# BpodTeensyShield.net
KiCad netlist of a schematic drawn in EAGLE
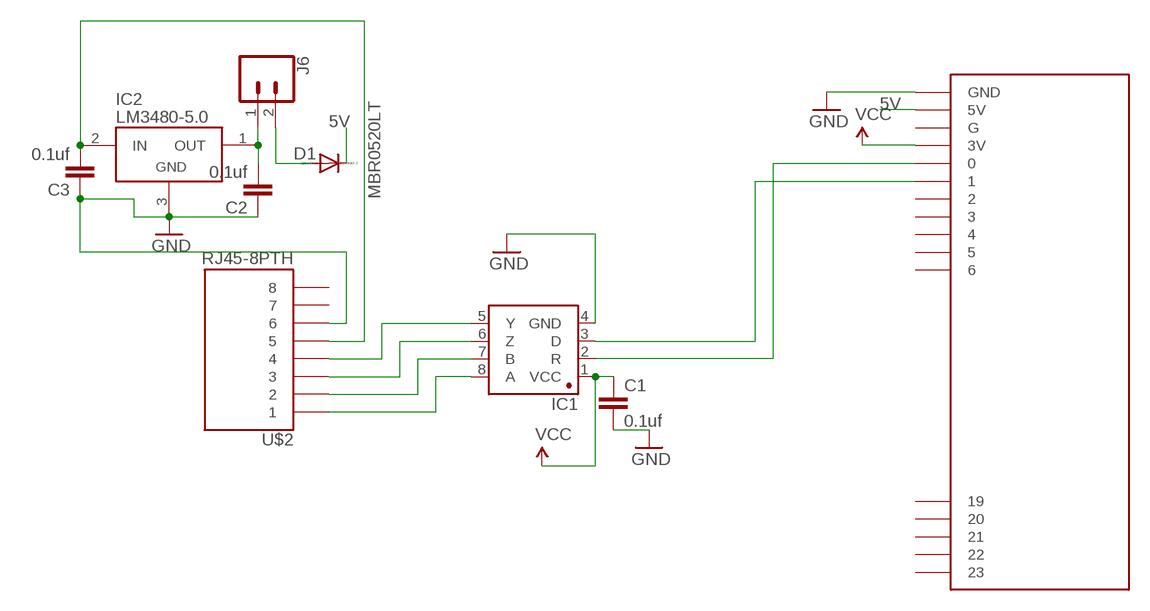
[diagram p0: schematic, sheet 1]

(export (version "E")
  (design (tool "Eeschema 10.0.6"))
  (components
    (comp (ref "C1")
      (value "0.1uf")
      (footprint "eagle-import:1206@1")
      (libsource (lib "eagle-import") (part "CAP1206"))
    )
    (comp (ref "C2")
      (value "0.1uf")
      (footprint "eagle-import:1206@1")
      (libsource (lib "eagle-import") (part "CAP1206"))
    )
    (comp (ref "C3")
      (value "0.1uf")
      (footprint "eagle-import:1206@1")
      (libsource (lib "eagle-import") (part "CAP1206"))
    )
    (comp (ref "D1")
      (value "MBR0520LT")
      (footprint "eagle-import:SOD123")
      (libsource (lib "eagle-import") (part "MBR0520LT"))
    )
    (comp (ref "IC1")
      (value "SN65HVD31DR")
      (footprint "eagle-import:SO08")
      (libsource (lib "eagle-import") (part "SN65HVD31DR"))
    )
    (comp (ref "IC2")
      (value "LM3480-5.0")
      (footprint "eagle-import:SOT-23-3")
      (libsource (lib "eagle-import") (part "LM3480-5.0"))
    )
    (comp (ref "J6")
      (value "CONN_02")
      (footprint "eagle-import:1X02")
      (libsource (lib "eagle-import") (part "CONN_02"))
    )
    (comp (ref "U$1")
      (value "AUDIOSHIELD")
      (footprint "eagle-import:AUDIOSHIELD")
      (libsource (lib "eagle-import") (part "AUDIOSHIELD"))
    )
    (comp (ref "U$2")
      (value "RJ45-8PTH")
      (footprint "eagle-import:RJ45-8")
      (libsource (lib "eagle-import") (part "RJ45-8PTH"))
    )
  )
  (nets
    (net (code "1") (name "/5V") (class "Default")
      (node (ref "D1") (pin "C") (pinfunction "C_C") (pintype "passive"))
      (node (ref "U$1") (pin "5V") (pinfunction "5V_5V") (pintype "bidirectional"))
    )
    (net (code "2") (name "GND") (class "Default")
      (node (ref "C1") (pin "2") (pinfunction "2_2") (pintype "passive"))
      (node (ref "C2") (pin "1") (pinfunction "1_1") (pintype "passive"))
      (node (ref "C3") (pin "1") (pinfunction "1_1") (pintype "passive"))
      (node (ref "IC1") (pin "4") (pinfunction "GND_4") (pintype "bidirectional"))
      (node (ref "IC2") (pin "3") (pinfunction "GND_3") (pintype "power_in"))
      (node (ref "U$1") (pin "GND") (pinfunction "GND_GND") (pintype "bidirectional"))
      (node (ref "U$2") (pin "6") (pinfunction "6_6") (pintype "bidirectional"))
    )
    (net (code "3") (name "Net-(D1-PadA)") (class "Default")
      (node (ref "D1") (pin "A") (pinfunction "A_A") (pintype "passive"))
      (node (ref "J6") (pin "2") (pinfunction "2_2") (pintype "passive"))
    )
    (net (code "4") (name "Net-(IC1-A)") (class "Default")
      (node (ref "IC1") (pin "8") (pinfunction "A_8") (pintype "bidirectional"))
      (node (ref "U$2") (pin "1") (pinfunction "1_1") (pintype "bidirectional"))
    )
    (net (code "5") (name "Net-(IC1-B)") (class "Default")
      (node (ref "IC1") (pin "7") (pinfunction "B_7") (pintype "bidirectional"))
      (node (ref "U$2") (pin "2") (pinfunction "2_2") (pintype "bidirectional"))
    )
    (net (code "6") (name "Net-(IC1-D)") (class "Default")
      (node (ref "IC1") (pin "3") (pinfunction "D_3") (pintype "bidirectional"))
      (node (ref "U$1") (pin "1") (pinfunction "1_1") (pintype "bidirectional"))
    )
    (net (code "7") (name "Net-(IC1-R)") (class "Default")
      (node (ref "IC1") (pin "2") (pinfunction "R_2") (pintype "bidirectional"))
      (node (ref "U$1") (pin "0") (pinfunction "0_0") (pintype "bidirectional"))
    )
    (net (code "8") (name "Net-(IC1-Y)") (class "Default")
      (node (ref "IC1") (pin "5") (pinfunction "Y_5") (pintype "bidirectional"))
      (node (ref "U$2") (pin "4") (pinfunction "4_4") (pintype "bidirectional"))
    )
    (net (code "9") (name "Net-(IC1-Z)") (class "Default")
      (node (ref "IC1") (pin "6") (pinfunction "Z_6") (pintype "bidirectional"))
      (node (ref "U$2") (pin "3") (pinfunction "3_3") (pintype "bidirectional"))
    )
    (net (code "10") (name "Net-(IC2-IN)") (class "Default")
      (node (ref "C3") (pin "2") (pinfunction "2_2") (pintype "passive"))
      (node (ref "IC2") (pin "2") (pinfunction "IN_2") (pintype "power_in"))
      (node (ref "U$2") (pin "5") (pinfunction "5_5") (pintype "bidirectional"))
    )
    (net (code "11") (name "Net-(IC2-OUT)") (class "Default")
      (node (ref "C2") (pin "2") (pinfunction "2_2") (pintype "passive"))
      (node (ref "IC2") (pin "1") (pinfunction "OUT_1") (pintype "power_in"))
      (node (ref "J6") (pin "1") (pinfunction "1_1") (pintype "passive"))
    )
    (net (code "12") (name "VCC") (class "Default")
      (node (ref "C1") (pin "1") (pinfunction "1_1") (pintype "passive"))
      (node (ref "IC1") (pin "1") (pinfunction "VCC_1") (pintype "bidirectional"))
      (node (ref "U$1") (pin "3V") (pinfunction "3V_3V") (pintype "bidirectional"))
    )
    (net (code "13") (name "unconnected-(U$1-Pad2)") (class "Default")
      (node (ref "U$1") (pin "2") (pinfunction "2_2") (pintype "bidirectional"))
    )
    (net (code "14") (name "unconnected-(U$1-Pad3)") (class "Default")
      (node (ref "U$1") (pin "3") (pinfunction "3_3") (pintype "bidirectional"))
    )
    (net (code "15") (name "unconnected-(U$1-Pad4)") (class "Default")
      (node (ref "U$1") (pin "4") (pinfunction "4_4") (pintype "bidirectional"))
    )
    (net (code "16") (name "unconnected-(U$1-Pad5)") (class "Default")
      (node (ref "U$1") (pin "5") (pinfunction "5_5") (pintype "bidirectional"))
    )
    (net (code "17") (name "unconnected-(U$1-Pad6)") (class "Default")
      (node (ref "U$1") (pin "6") (pinfunction "6_6") (pintype "bidirectional"))
    )
    (net (code "18") (name "unconnected-(U$1-Pad19)") (class "Default")
      (node (ref "U$1") (pin "19") (pinfunction "19_19") (pintype "bidirectional"))
    )
    (net (code "19") (name "unconnected-(U$1-Pad20)") (class "Default")
      (node (ref "U$1") (pin "20") (pinfunction "20_20") (pintype "bidirectional"))
    )
    (net (code "20") (name "unconnected-(U$1-Pad21)") (class "Default")
      (node (ref "U$1") (pin "21") (pinfunction "21_21") (pintype "bidirectional"))
    )
    (net (code "21") (name "unconnected-(U$1-Pad22)") (class "Default")
      (node (ref "U$1") (pin "22") (pinfunction "22_22") (pintype "bidirectional"))
    )
    (net (code "22") (name "unconnected-(U$1-Pad23)") (class "Default")
      (node (ref "U$1") (pin "23") (pinfunction "23_23") (pintype "bidirectional"))
    )
    (net (code "23") (name "unconnected-(U$1-PadG)") (class "Default")
      (node (ref "U$1") (pin "G") (pinfunction "G_G") (pintype "bidirectional"))
    )
    (net (code "24") (name "unconnected-(U$2-Pad7)") (class "Default")
      (node (ref "U$2") (pin "7") (pinfunction "7_7") (pintype "bidirectional"))
    )
    (net (code "25") (name "unconnected-(U$2-Pad8)") (class "Default")
      (node (ref "U$2") (pin "8") (pinfunction "8_8") (pintype "bidirectional"))
    )
  )
)
